# pyPhotometry_1_0_2.net
KiCad netlist of a schematic drawn in EAGLE
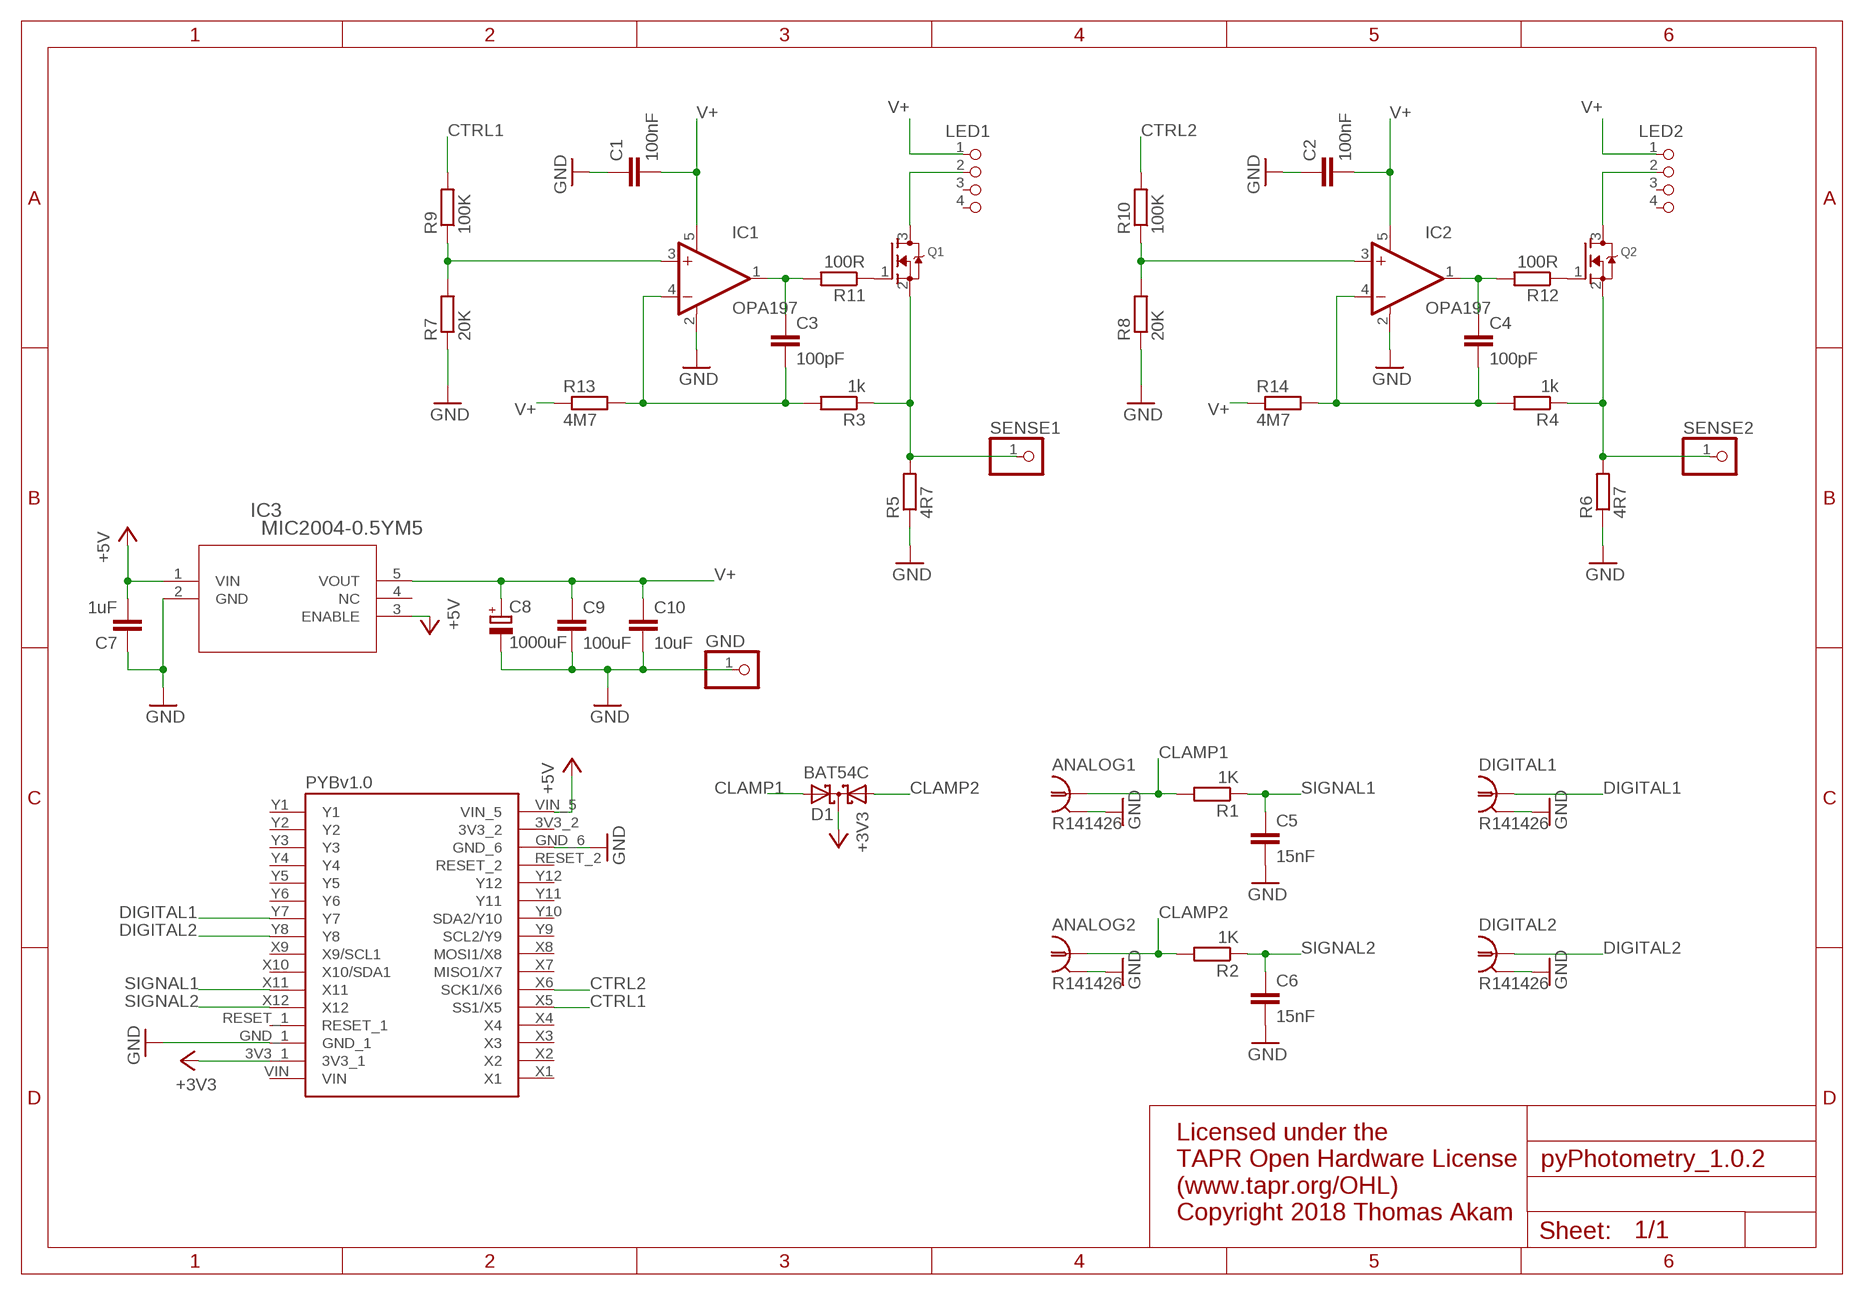
[diagram p0: schematic, sheet 1]

(export (version "E")
  (design (tool "Eeschema 10.0.6"))
  (components
    (comp (ref "ANALOG1")
      (value "R141426")
      (footprint "eagle-import:R141426")
      (fields (field (name "MF") "FARNELL") (field (name "MPN") "R141426161"))
      (libsource (lib "eagle-import") (part "R141426"))
    )
    (comp (ref "ANALOG2")
      (value "R141426")
      (footprint "eagle-import:R141426")
      (fields (field (name "MF") "FARNELL") (field (name "MPN") "R141426161"))
      (libsource (lib "eagle-import") (part "R141426"))
    )
    (comp (ref "C1")
      (value "100nF")
      (footprint "eagle-import:C0805")
      (libsource (lib "eagle-import") (part "C-EUC0805"))
    )
    (comp (ref "C2")
      (value "100nF")
      (footprint "eagle-import:C0805")
      (libsource (lib "eagle-import") (part "C-EUC0805"))
    )
    (comp (ref "C3")
      (value "100pF")
      (footprint "eagle-import:C0805")
      (libsource (lib "eagle-import") (part "C-EUC0805"))
    )
    (comp (ref "C4")
      (value "100pF")
      (footprint "eagle-import:C0805")
      (libsource (lib "eagle-import") (part "C-EUC0805"))
    )
    (comp (ref "C5")
      (value "15nF")
      (footprint "eagle-import:C0805")
      (libsource (lib "eagle-import") (part "C-EUC0805"))
    )
    (comp (ref "C6")
      (value "15nF")
      (footprint "eagle-import:C0805")
      (libsource (lib "eagle-import") (part "C-EUC0805"))
    )
    (comp (ref "C7")
      (value "1uF")
      (footprint "eagle-import:C0805")
      (libsource (lib "eagle-import") (part "C-EUC0805"))
    )
    (comp (ref "C8")
      (value "1000uF")
      (footprint "eagle-import:153CLV-0807")
      (libsource (lib "eagle-import") (part "CPOL-EU153CLV-0807"))
    )
    (comp (ref "C9")
      (value "100uF")
      (footprint "eagle-import:C1206")
      (libsource (lib "eagle-import") (part "C-EUC1206"))
    )
    (comp (ref "C10")
      (value "10uF")
      (footprint "eagle-import:C1206")
      (libsource (lib "eagle-import") (part "C-EUC1206"))
    )
    (comp (ref "D1")
      (value "BAT54C")
      (footprint "eagle-import:SOT23")
      (libsource (lib "eagle-import") (part "BAT54C"))
    )
    (comp (ref "DIGITAL1")
      (value "R141426")
      (footprint "eagle-import:R141426")
      (fields (field (name "MF") "FARNELL") (field (name "MPN") "R141426161"))
      (libsource (lib "eagle-import") (part "R141426"))
    )
    (comp (ref "DIGITAL2")
      (value "R141426")
      (footprint "eagle-import:R141426")
      (fields (field (name "MF") "FARNELL") (field (name "MPN") "R141426161"))
      (libsource (lib "eagle-import") (part "R141426"))
    )
    (comp (ref "GND")
      (value "PINHD-1X1")
      (footprint "eagle-import:1X01")
      (libsource (lib "eagle-import") (part "PINHD-1X1"))
    )
    (comp (ref "IC1")
      (value "OPA197")
      (footprint "eagle-import:SOT23-5")
      (libsource (lib "eagle-import") (part "OPA197"))
    )
    (comp (ref "IC2")
      (value "OPA197")
      (footprint "eagle-import:SOT23-5")
      (libsource (lib "eagle-import") (part "OPA197"))
    )
    (comp (ref "IC3")
      (value "MIC2004-0.5YM5")
      (footprint "eagle-import:SOT-23-5_M5")
      (fields (field (name "MANUFACTURER_PART_NUMBER") "MIC20040.5YM5"))
      (libsource (lib "eagle-import") (part "MIC2004-0.5YM5"))
    )
    (comp (ref "LED1")
      (value "M8-4")
      (footprint "eagle-import:M8-4")
      (libsource (lib "eagle-import") (part "M8-4"))
    )
    (comp (ref "LED2")
      (value "M8-4")
      (footprint "eagle-import:M8-4")
      (libsource (lib "eagle-import") (part "M8-4"))
    )
    (comp (ref "Q1")
      (value "MOSFET-NREFLOW")
      (footprint "eagle-import:SOT23")
      (libsource (lib "eagle-import") (part "MOSFET-NREFLOW"))
    )
    (comp (ref "Q2")
      (value "MOSFET-NREFLOW")
      (footprint "eagle-import:SOT23")
      (libsource (lib "eagle-import") (part "MOSFET-NREFLOW"))
    )
    (comp (ref "R1")
      (value "1K")
      (footprint "eagle-import:M0805")
      (libsource (lib "eagle-import") (part "R-EU_M0805"))
    )
    (comp (ref "R2")
      (value "1K")
      (footprint "eagle-import:M0805")
      (libsource (lib "eagle-import") (part "R-EU_M0805"))
    )
    (comp (ref "R3")
      (value "1k")
      (footprint "eagle-import:R0805")
      (libsource (lib "eagle-import") (part "R-EU_R0805"))
    )
    (comp (ref "R4")
      (value "1k")
      (footprint "eagle-import:R0805")
      (libsource (lib "eagle-import") (part "R-EU_R0805"))
    )
    (comp (ref "R5")
      (value "4R7")
      (footprint "eagle-import:M0805")
      (libsource (lib "eagle-import") (part "R-EU_M0805"))
    )
    (comp (ref "R6")
      (value "4R7")
      (footprint "eagle-import:M0805")
      (libsource (lib "eagle-import") (part "R-EU_M0805"))
    )
    (comp (ref "R7")
      (value "20K")
      (footprint "eagle-import:R0805")
      (libsource (lib "eagle-import") (part "R-EU_R0805"))
    )
    (comp (ref "R8")
      (value "20K")
      (footprint "eagle-import:R0805")
      (libsource (lib "eagle-import") (part "R-EU_R0805"))
    )
    (comp (ref "R9")
      (value "100K")
      (footprint "eagle-import:R0805")
      (libsource (lib "eagle-import") (part "R-EU_R0805"))
    )
    (comp (ref "R10")
      (value "100K")
      (footprint "eagle-import:R0805")
      (libsource (lib "eagle-import") (part "R-EU_R0805"))
    )
    (comp (ref "R11")
      (value "100R")
      (footprint "eagle-import:R0805")
      (libsource (lib "eagle-import") (part "R-EU_R0805"))
    )
    (comp (ref "R12")
      (value "100R")
      (footprint "eagle-import:R0805")
      (libsource (lib "eagle-import") (part "R-EU_R0805"))
    )
    (comp (ref "R13")
      (value "4M7")
      (footprint "eagle-import:M0805")
      (libsource (lib "eagle-import") (part "R-EU_M0805"))
    )
    (comp (ref "R14")
      (value "4M7")
      (footprint "eagle-import:M0805")
      (libsource (lib "eagle-import") (part "R-EU_M0805"))
    )
    (comp (ref "SENSE1")
      (value "PINHD-1X1")
      (footprint "eagle-import:1X01")
      (libsource (lib "eagle-import") (part "PINHD-1X1"))
    )
    (comp (ref "SENSE2")
      (value "PINHD-1X1")
      (footprint "eagle-import:1X01")
      (libsource (lib "eagle-import") (part "PINHD-1X1"))
    )
    (comp (ref "U$1")
      (value "PYBOARD-REDUCED-3")
      (footprint "eagle-import:PYBOARD-REDUCED-3")
      (libsource (lib "eagle-import") (part "PYBOARD-REDUCED-3"))
    )
  )
  (nets
    (net (code "1") (name "+3V3") (class "Default")
      (node (ref "D1") (pin "3") (pinfunction "CC_3") (pintype "passive"))
      (node (ref "U$1") (pin "3V3_1") (pinfunction "3V3_1_3V3_1") (pintype "bidirectional"))
    )
    (net (code "2") (name "+5V") (class "Default")
      (node (ref "C7") (pin "2") (pinfunction "2_2") (pintype "passive"))
      (node (ref "IC3") (pin "1") (pinfunction "VIN_1") (pintype "input"))
      (node (ref "IC3") (pin "3") (pinfunction "ENABLE_3") (pintype "input"))
      (node (ref "U$1") (pin "VIN_5") (pinfunction "VIN_5_VIN_5") (pintype "bidirectional"))
    )
    (net (code "3") (name "/CLAMP1") (class "Default")
      (node (ref "ANALOG1") (pin "1") (pinfunction "1_1") (pintype "passive"))
      (node (ref "D1") (pin "2") (pinfunction "A2_2") (pintype "passive"))
      (node (ref "R1") (pin "2") (pinfunction "2_2") (pintype "passive"))
    )
    (net (code "4") (name "/CLAMP2") (class "Default")
      (node (ref "ANALOG2") (pin "1") (pinfunction "1_1") (pintype "passive"))
      (node (ref "D1") (pin "1") (pinfunction "A1_1") (pintype "passive"))
      (node (ref "R2") (pin "2") (pinfunction "2_2") (pintype "passive"))
    )
    (net (code "5") (name "/CTRL1") (class "Default")
      (node (ref "R9") (pin "2") (pinfunction "2_2") (pintype "passive"))
      (node (ref "U$1") (pin "X5") (pinfunction "SS1/X5_X5") (pintype "bidirectional"))
    )
    (net (code "6") (name "/CTRL2") (class "Default")
      (node (ref "R10") (pin "2") (pinfunction "2_2") (pintype "passive"))
      (node (ref "U$1") (pin "X6") (pinfunction "SCK1/X6_X6") (pintype "bidirectional"))
    )
    (net (code "7") (name "/DIGITAL1") (class "Default")
      (node (ref "DIGITAL1") (pin "1") (pinfunction "1_1") (pintype "passive"))
      (node (ref "U$1") (pin "Y7") (pinfunction "Y7_Y7") (pintype "bidirectional"))
    )
    (net (code "8") (name "/DIGITAL2") (class "Default")
      (node (ref "DIGITAL2") (pin "1") (pinfunction "1_1") (pintype "passive"))
      (node (ref "U$1") (pin "Y8") (pinfunction "Y8_Y8") (pintype "bidirectional"))
    )
    (net (code "9") (name "/SIGNAL1") (class "Default")
      (node (ref "C5") (pin "1") (pinfunction "1_1") (pintype "passive"))
      (node (ref "R1") (pin "1") (pinfunction "1_1") (pintype "passive"))
      (node (ref "U$1") (pin "X11") (pinfunction "X11_X11") (pintype "bidirectional"))
    )
    (net (code "10") (name "/SIGNAL2") (class "Default")
      (node (ref "C6") (pin "1") (pinfunction "1_1") (pintype "passive"))
      (node (ref "R2") (pin "1") (pinfunction "1_1") (pintype "passive"))
      (node (ref "U$1") (pin "X12") (pinfunction "X12_X12") (pintype "bidirectional"))
    )
    (net (code "11") (name "/V+") (class "Default")
      (node (ref "C1") (pin "2") (pinfunction "2_2") (pintype "passive"))
      (node (ref "C10") (pin "1") (pinfunction "1_1") (pintype "passive"))
      (node (ref "C2") (pin "2") (pinfunction "2_2") (pintype "passive"))
      (node (ref "C8") (pin "+") (pinfunction "+_+") (pintype "passive"))
      (node (ref "C9") (pin "1") (pinfunction "1_1") (pintype "passive"))
      (node (ref "IC1") (pin "5") (pinfunction "V+_5") (pintype "power_in"))
      (node (ref "IC2") (pin "5") (pinfunction "V+_5") (pintype "power_in"))
      (node (ref "IC3") (pin "5") (pinfunction "VOUT_5") (pintype "output"))
      (node (ref "LED1") (pin "1") (pinfunction "1_1") (pintype "passive"))
      (node (ref "LED2") (pin "1") (pinfunction "1_1") (pintype "passive"))
      (node (ref "R13") (pin "1") (pinfunction "1_1") (pintype "passive"))
      (node (ref "R14") (pin "1") (pinfunction "1_1") (pintype "passive"))
    )
    (net (code "12") (name "GND") (class "Default")
      (node (ref "ANALOG1") (pin "2") (pinfunction "GND_2") (pintype "power_in"))
      (node (ref "ANALOG2") (pin "2") (pinfunction "GND_2") (pintype "power_in"))
      (node (ref "C1") (pin "1") (pinfunction "1_1") (pintype "passive"))
      (node (ref "C10") (pin "2") (pinfunction "2_2") (pintype "passive"))
      (node (ref "C2") (pin "1") (pinfunction "1_1") (pintype "passive"))
      (node (ref "C5") (pin "2") (pinfunction "2_2") (pintype "passive"))
      (node (ref "C6") (pin "2") (pinfunction "2_2") (pintype "passive"))
      (node (ref "C7") (pin "1") (pinfunction "1_1") (pintype "passive"))
      (node (ref "C8") (pin "-") (pinfunction "-_-") (pintype "passive"))
      (node (ref "C9") (pin "2") (pinfunction "2_2") (pintype "passive"))
      (node (ref "DIGITAL1") (pin "2") (pinfunction "GND_2") (pintype "power_in"))
      (node (ref "DIGITAL2") (pin "2") (pinfunction "GND_2") (pintype "power_in"))
      (node (ref "GND") (pin "1") (pinfunction "1_1") (pintype "passive"))
      (node (ref "IC1") (pin "2") (pinfunction "V-_2") (pintype "power_in"))
      (node (ref "IC2") (pin "2") (pinfunction "V-_2") (pintype "power_in"))
      (node (ref "IC3") (pin "2") (pinfunction "GND_2") (pintype "power_in"))
      (node (ref "R5") (pin "1") (pinfunction "1_1") (pintype "passive"))
      (node (ref "R6") (pin "1") (pinfunction "1_1") (pintype "passive"))
      (node (ref "R7") (pin "1") (pinfunction "1_1") (pintype "passive"))
      (node (ref "R8") (pin "1") (pinfunction "1_1") (pintype "passive"))
      (node (ref "U$1") (pin "GND_1") (pinfunction "GND_1_GND_1") (pintype "bidirectional"))
      (node (ref "U$1") (pin "GND_6") (pinfunction "GND_6_GND_6") (pintype "bidirectional"))
    )
    (net (code "13") (name "Net-(IC1-+IN)") (class "Default")
      (node (ref "IC1") (pin "3") (pinfunction "+IN_3") (pintype "input"))
      (node (ref "R7") (pin "2") (pinfunction "2_2") (pintype "passive"))
      (node (ref "R9") (pin "1") (pinfunction "1_1") (pintype "passive"))
    )
    (net (code "14") (name "Net-(IC1--IN)") (class "Default")
      (node (ref "C3") (pin "2") (pinfunction "2_2") (pintype "passive"))
      (node (ref "IC1") (pin "4") (pinfunction "-IN_4") (pintype "input"))
      (node (ref "R13") (pin "2") (pinfunction "2_2") (pintype "passive"))
      (node (ref "R3") (pin "2") (pinfunction "2_2") (pintype "passive"))
    )
    (net (code "15") (name "Net-(IC1-OUT)") (class "Default")
      (node (ref "C3") (pin "1") (pinfunction "1_1") (pintype "passive"))
      (node (ref "IC1") (pin "1") (pinfunction "OUT_1") (pintype "output"))
      (node (ref "R11") (pin "2") (pinfunction "2_2") (pintype "passive"))
    )
    (net (code "16") (name "Net-(IC2-+IN)") (class "Default")
      (node (ref "IC2") (pin "3") (pinfunction "+IN_3") (pintype "input"))
      (node (ref "R10") (pin "1") (pinfunction "1_1") (pintype "passive"))
      (node (ref "R8") (pin "2") (pinfunction "2_2") (pintype "passive"))
    )
    (net (code "17") (name "Net-(IC2--IN)") (class "Default")
      (node (ref "C4") (pin "2") (pinfunction "2_2") (pintype "passive"))
      (node (ref "IC2") (pin "4") (pinfunction "-IN_4") (pintype "input"))
      (node (ref "R14") (pin "2") (pinfunction "2_2") (pintype "passive"))
      (node (ref "R4") (pin "2") (pinfunction "2_2") (pintype "passive"))
    )
    (net (code "18") (name "Net-(IC2-OUT)") (class "Default")
      (node (ref "C4") (pin "1") (pinfunction "1_1") (pintype "passive"))
      (node (ref "IC2") (pin "1") (pinfunction "OUT_1") (pintype "output"))
      (node (ref "R12") (pin "2") (pinfunction "2_2") (pintype "passive"))
    )
    (net (code "19") (name "Net-(Q1-D)") (class "Default")
      (node (ref "LED1") (pin "2") (pinfunction "2_2") (pintype "passive"))
      (node (ref "Q1") (pin "3") (pinfunction "D_3") (pintype "bidirectional"))
    )
    (net (code "20") (name "Net-(Q1-G)") (class "Default")
      (node (ref "Q1") (pin "1") (pinfunction "G_1") (pintype "bidirectional"))
      (node (ref "R11") (pin "1") (pinfunction "1_1") (pintype "passive"))
    )
    (net (code "21") (name "Net-(Q1-S)") (class "Default")
      (node (ref "Q1") (pin "2") (pinfunction "S_2") (pintype "bidirectional"))
      (node (ref "R3") (pin "1") (pinfunction "1_1") (pintype "passive"))
      (node (ref "R5") (pin "2") (pinfunction "2_2") (pintype "passive"))
      (node (ref "SENSE1") (pin "1") (pinfunction "1_1") (pintype "passive"))
    )
    (net (code "22") (name "Net-(Q2-D)") (class "Default")
      (node (ref "LED2") (pin "2") (pinfunction "2_2") (pintype "passive"))
      (node (ref "Q2") (pin "3") (pinfunction "D_3") (pintype "bidirectional"))
    )
    (net (code "23") (name "Net-(Q2-G)") (class "Default")
      (node (ref "Q2") (pin "1") (pinfunction "G_1") (pintype "bidirectional"))
      (node (ref "R12") (pin "1") (pinfunction "1_1") (pintype "passive"))
    )
    (net (code "24") (name "Net-(Q2-S)") (class "Default")
      (node (ref "Q2") (pin "2") (pinfunction "S_2") (pintype "bidirectional"))
      (node (ref "R4") (pin "1") (pinfunction "1_1") (pintype "passive"))
      (node (ref "R6") (pin "2") (pinfunction "2_2") (pintype "passive"))
      (node (ref "SENSE2") (pin "1") (pinfunction "1_1") (pintype "passive"))
    )
    (net (code "25") (name "unconnected-(IC3-NC-Pad4)") (class "Default")
      (node (ref "IC3") (pin "4") (pinfunction "NC_4") (pintype "no_connect"))
    )
    (net (code "26") (name "unconnected-(LED1-Pad3)") (class "Default")
      (node (ref "LED1") (pin "3") (pinfunction "3_3") (pintype "passive"))
    )
    (net (code "27") (name "unconnected-(LED1-Pad4)") (class "Default")
      (node (ref "LED1") (pin "4") (pinfunction "4_4") (pintype "passive"))
    )
    (net (code "28") (name "unconnected-(LED2-Pad3)") (class "Default")
      (node (ref "LED2") (pin "3") (pinfunction "3_3") (pintype "passive"))
    )
    (net (code "29") (name "unconnected-(LED2-Pad4)") (class "Default")
      (node (ref "LED2") (pin "4") (pinfunction "4_4") (pintype "passive"))
    )
    (net (code "30") (name "unconnected-(U$1-MISO1{slash}X7-PadX7)") (class "Default")
      (node (ref "U$1") (pin "X7") (pinfunction "MISO1/X7_X7") (pintype "bidirectional"))
    )
    (net (code "31") (name "unconnected-(U$1-MOSI1{slash}X8-PadX8)") (class "Default")
      (node (ref "U$1") (pin "X8") (pinfunction "MOSI1/X8_X8") (pintype "bidirectional"))
    )
    (net (code "32") (name "unconnected-(U$1-Pad3V3_2)") (class "Default")
      (node (ref "U$1") (pin "3V3_2") (pinfunction "3V3_2_3V3_2") (pintype "bidirectional"))
    )
    (net (code "33") (name "unconnected-(U$1-PadRESET_1)") (class "Default")
      (node (ref "U$1") (pin "RESET_1") (pinfunction "RESET_1_RESET_1") (pintype "bidirectional"))
    )
    (net (code "34") (name "unconnected-(U$1-PadRESET_2)") (class "Default")
      (node (ref "U$1") (pin "RESET_2") (pinfunction "RESET_2_RESET_2") (pintype "bidirectional"))
    )
    (net (code "35") (name "unconnected-(U$1-PadVIN)") (class "Default")
      (node (ref "U$1") (pin "VIN") (pinfunction "VIN_VIN") (pintype "bidirectional"))
    )
    (net (code "36") (name "unconnected-(U$1-PadX1)") (class "Default")
      (node (ref "U$1") (pin "X1") (pinfunction "X1_X1") (pintype "bidirectional"))
    )
    (net (code "37") (name "unconnected-(U$1-PadX2)") (class "Default")
      (node (ref "U$1") (pin "X2") (pinfunction "X2_X2") (pintype "bidirectional"))
    )
    (net (code "38") (name "unconnected-(U$1-PadX3)") (class "Default")
      (node (ref "U$1") (pin "X3") (pinfunction "X3_X3") (pintype "bidirectional"))
    )
    (net (code "39") (name "unconnected-(U$1-PadX4)") (class "Default")
      (node (ref "U$1") (pin "X4") (pinfunction "X4_X4") (pintype "bidirectional"))
    )
    (net (code "40") (name "unconnected-(U$1-PadY1)") (class "Default")
      (node (ref "U$1") (pin "Y1") (pinfunction "Y1_Y1") (pintype "bidirectional"))
    )
    (net (code "41") (name "unconnected-(U$1-PadY2)") (class "Default")
      (node (ref "U$1") (pin "Y2") (pinfunction "Y2_Y2") (pintype "bidirectional"))
    )
    (net (code "42") (name "unconnected-(U$1-PadY3)") (class "Default")
      (node (ref "U$1") (pin "Y3") (pinfunction "Y3_Y3") (pintype "bidirectional"))
    )
    (net (code "43") (name "unconnected-(U$1-PadY4)") (class "Default")
      (node (ref "U$1") (pin "Y4") (pinfunction "Y4_Y4") (pintype "bidirectional"))
    )
    (net (code "44") (name "unconnected-(U$1-PadY5)") (class "Default")
      (node (ref "U$1") (pin "Y5") (pinfunction "Y5_Y5") (pintype "bidirectional"))
    )
    (net (code "45") (name "unconnected-(U$1-PadY6)") (class "Default")
      (node (ref "U$1") (pin "Y6") (pinfunction "Y6_Y6") (pintype "bidirectional"))
    )
    (net (code "46") (name "unconnected-(U$1-PadY11)") (class "Default")
      (node (ref "U$1") (pin "Y11") (pinfunction "Y11_Y11") (pintype "bidirectional"))
    )
    (net (code "47") (name "unconnected-(U$1-PadY12)") (class "Default")
      (node (ref "U$1") (pin "Y12") (pinfunction "Y12_Y12") (pintype "bidirectional"))
    )
    (net (code "48") (name "unconnected-(U$1-SCL2{slash}Y9-PadY9)") (class "Default")
      (node (ref "U$1") (pin "Y9") (pinfunction "SCL2/Y9_Y9") (pintype "bidirectional"))
    )
    (net (code "49") (name "unconnected-(U$1-SDA2{slash}Y10-PadY10)") (class "Default")
      (node (ref "U$1") (pin "Y10") (pinfunction "SDA2/Y10_Y10") (pintype "bidirectional"))
    )
    (net (code "50") (name "unconnected-(U$1-X9{slash}SCL1-PadX9)") (class "Default")
      (node (ref "U$1") (pin "X9") (pinfunction "X9/SCL1_X9") (pintype "bidirectional"))
    )
    (net (code "51") (name "unconnected-(U$1-X10{slash}SDA1-PadX10)") (class "Default")
      (node (ref "U$1") (pin "X10") (pinfunction "X10/SDA1_X10") (pintype "bidirectional"))
    )
  )
)
